# 1-Schematic.net
KiCad netlist of a schematic drawn in EasyEDA
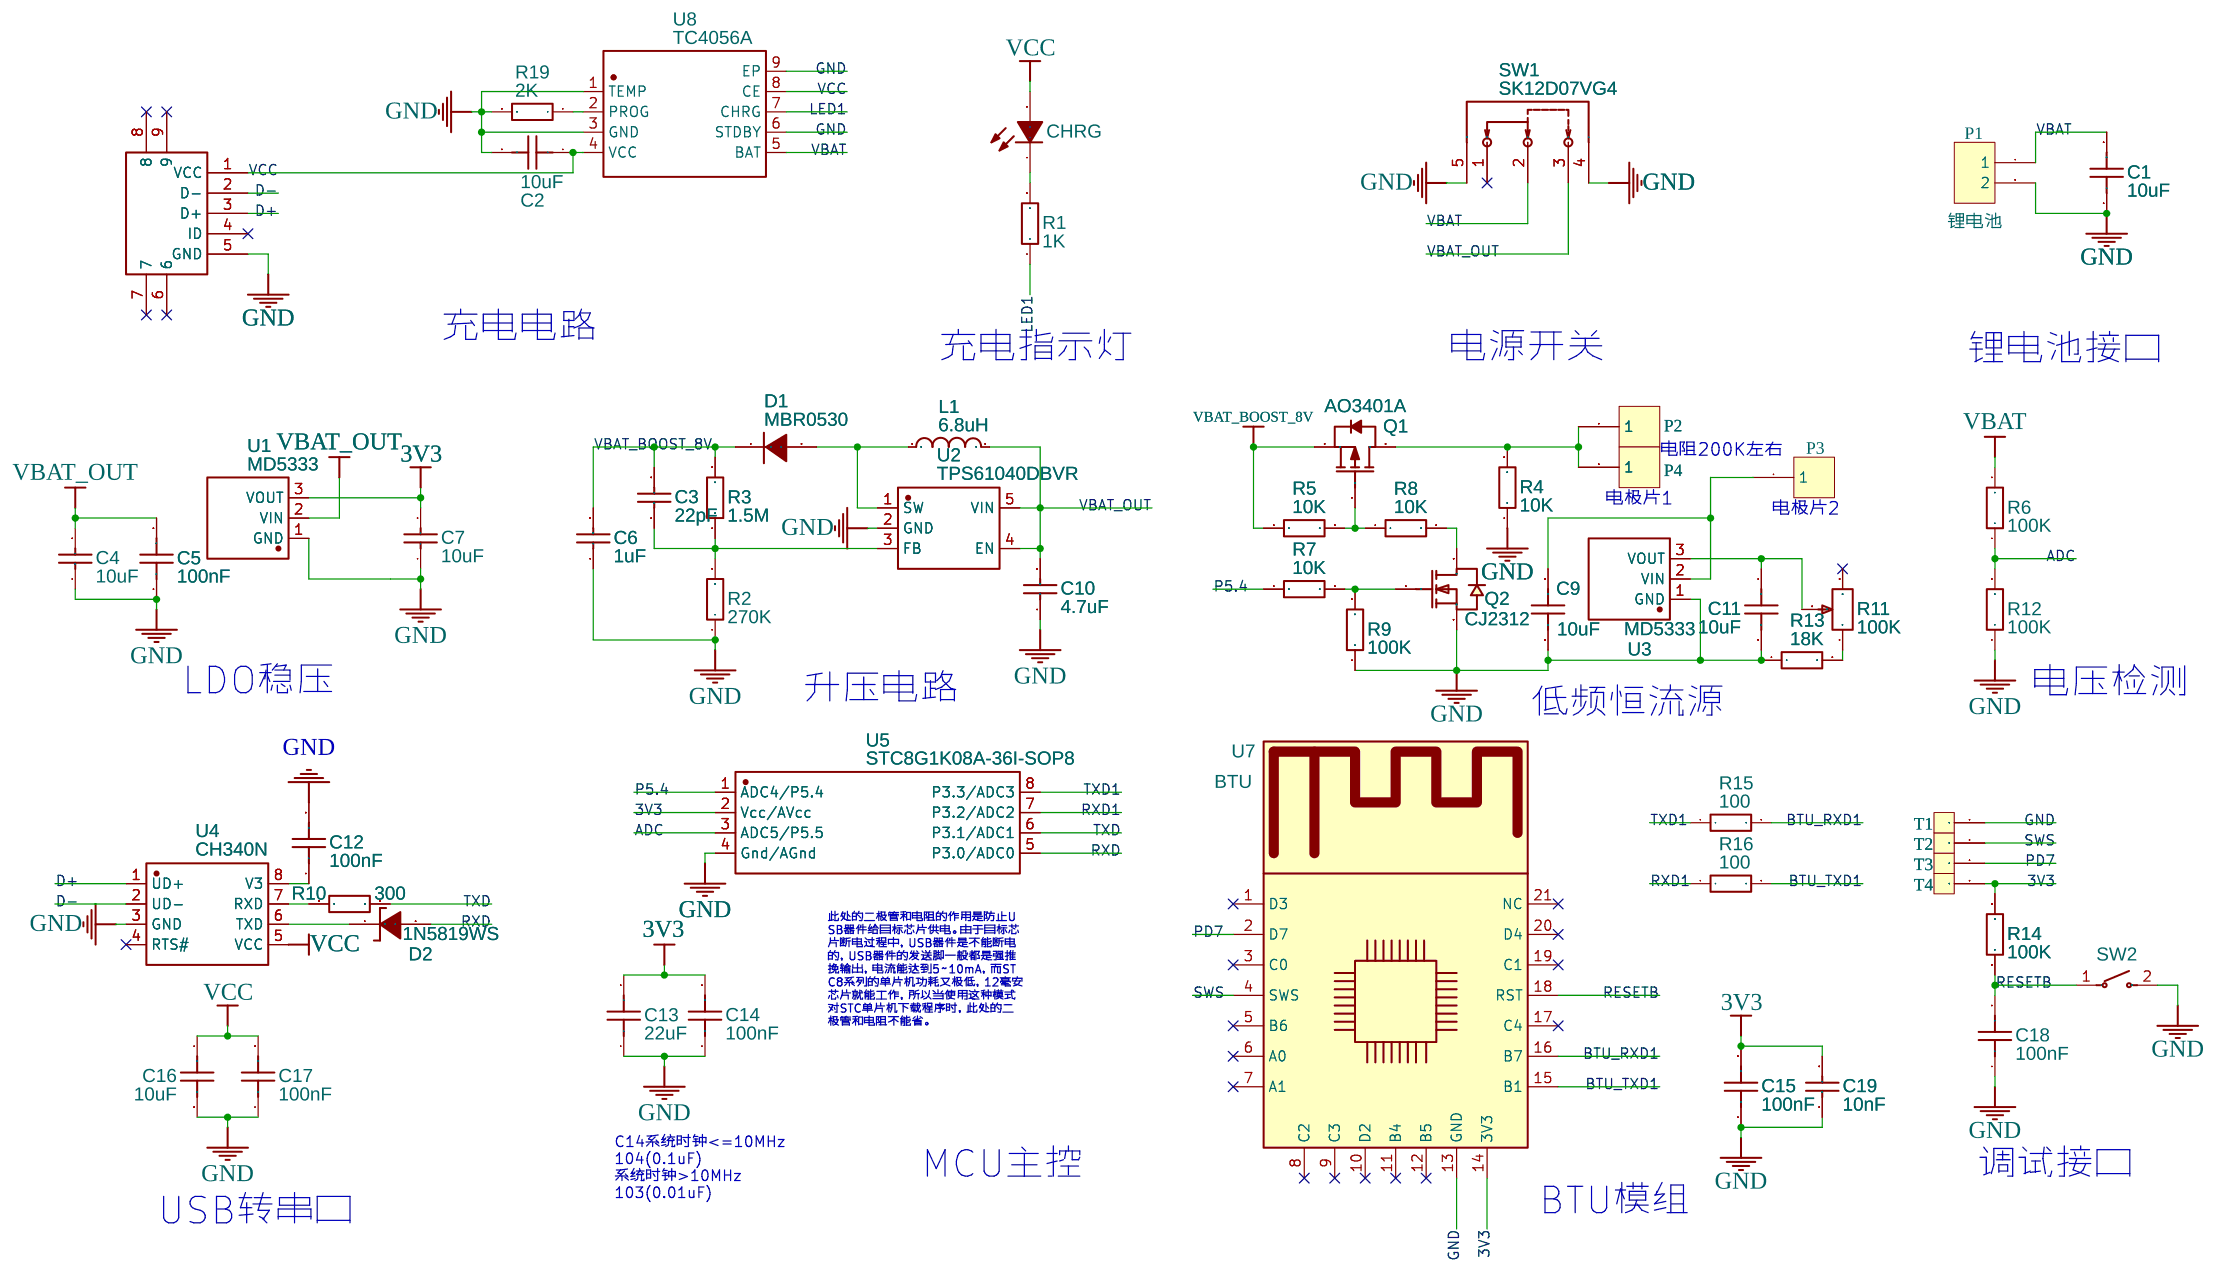
[diagram p0: schematic sheet]

(export (version "E")
  (design (tool "Eeschema 10.0.6"))
  (components
    (comp (ref "C1")
      (value "10uF")
      (fields
        (field (name "BOM_Manufacturer Part") "CL10A106KP8NNNC")
        (field (name "BOM_Supplier Part") "C19702")
      )
      (libsource (lib "") (part "CL10A106KP8NNNC_2"))
    )
    (comp (ref "C2")
      (value "10uF")
      (fields
        (field (name "BOM_Manufacturer Part") "CL10A106KP8NNNC")
        (field (name "BOM_Supplier Part") "C19702")
      )
      (libsource (lib "") (part "CL10A106KP8NNNC"))
    )
    (comp (ref "C3")
      (value "22pF")
      (fields
        (field (name "BOM_Manufacturer Part") "CC0603JRNPO9BN220")
        (field (name "BOM_Supplier Part") "C105620")
      )
      (libsource (lib "") (part "CC0603JRNPO9BN220"))
    )
    (comp (ref "C4")
      (value "10uF")
      (fields
        (field (name "BOM_Manufacturer Part") "CC0603MRX5R6BB106")
        (field (name "BOM_Supplier Part") "C109453")
      )
      (libsource (lib "") (part "CC0603MRX5R6BB106"))
    )
    (comp (ref "C5")
      (value "100nF")
      (fields
        (field (name "BOM_Manufacturer Part") "0603F104Z500")
        (field (name "BOM_Supplier Part") "C83060")
      )
      (libsource (lib "") (part "0603F104Z500"))
    )
    (comp (ref "C6")
      (value "1uF")
      (fields
        (field (name "BOM_Manufacturer Part") "CL10A105KO8NNNC")
        (field (name "BOM_Supplier Part") "C1592")
      )
      (libsource (lib "") (part "CL10A105KO8NNNC"))
    )
    (comp (ref "C7")
      (value "10uF")
      (fields
        (field (name "BOM_Manufacturer Part") "CC0603MRX5R6BB106")
        (field (name "BOM_Supplier Part") "C109453")
      )
      (libsource (lib "") (part "CC0603MRX5R6BB106"))
    )
    (comp (ref "C9")
      (value "10uF")
      (fields
        (field (name "BOM_Manufacturer Part") "CL10A106KP8NNNC")
        (field (name "BOM_Supplier Part") "C19702")
      )
      (libsource (lib "") (part "CL10A106KP8NNNC_1"))
    )
    (comp (ref "C10")
      (value "4.7uF")
      (fields
        (field (name "BOM_Manufacturer Part") "CL10A475KP8NNNC")
        (field (name "BOM_Supplier Part") "C1705")
      )
      (libsource (lib "") (part "CL10A475KP8NNNC"))
    )
    (comp (ref "C11")
      (value "10uF")
      (fields
        (field (name "BOM_Manufacturer Part") "CL10A106KP8NNNC")
        (field (name "BOM_Supplier Part") "C19702")
      )
      (libsource (lib "") (part "CL10A106KP8NNNC_1"))
    )
    (comp (ref "C12")
      (value "100nF")
      (fields
        (field (name "BOM_Manufacturer Part") "CC0603KRX7R9BB104")
        (field (name "BOM_Supplier Part") "C14663")
      )
      (libsource (lib "") (part "CC0603KRX7R9BB104"))
    )
    (comp (ref "C13")
      (value "22uF")
      (fields
        (field (name "BOM_Manufacturer Part") "CL10A226MQ8NRNC")
        (field (name "BOM_Supplier Part") "C59461")
      )
      (libsource (lib "") (part "CL10A226MQ8NRNC"))
    )
    (comp (ref "C14")
      (value "100nF")
      (fields
        (field (name "BOM_Manufacturer Part") "CC0603KRX7R9BB104")
        (field (name "BOM_Supplier Part") "C14663")
      )
      (libsource (lib "") (part "CC0603KRX7R9BB104"))
    )
    (comp (ref "C15")
      (value "100nF")
      (fields
        (field (name "BOM_Manufacturer Part") "CC0603KRX7R9BB104")
        (field (name "BOM_Supplier Part") "C14663")
      )
      (libsource (lib "") (part "CC0603KRX7R9BB104"))
    )
    (comp (ref "C16")
      (value "10uF")
      (fields
        (field (name "BOM_Manufacturer Part") "CL10A106KP8NNNC")
        (field (name "BOM_Supplier Part") "C19702")
      )
      (libsource (lib "") (part "CL10A106KP8NNNC_1"))
    )
    (comp (ref "C17")
      (value "100nF")
      (fields
        (field (name "BOM_Manufacturer Part") "CC0603KRX7R9BB104")
        (field (name "BOM_Supplier Part") "C14663")
      )
      (libsource (lib "") (part "CC0603KRX7R9BB104"))
    )
    (comp (ref "C18")
      (value "100nF")
      (fields
        (field (name "BOM_Manufacturer Part") "CC0603KRX7R9BB104")
        (field (name "BOM_Supplier Part") "C14663")
      )
      (libsource (lib "") (part "CC0603KRX7R9BB104"))
    )
    (comp (ref "C19")
      (value "10nF")
      (fields
        (field (name "BOM_Manufacturer Part") "CC0603KRX7R9BB103")
        (field (name "BOM_Supplier Part") "C100042")
      )
      (libsource (lib "") (part "CC0603KRX7R9BB103"))
    )
    (comp (ref "CHRG")
      (value "19-21SURC/S530-A2/TR8")
      (fields (field (name "BOM_Supplier Part") "C72045"))
      (libsource (lib "") (part "19-21SURC/S530-A2/TR8"))
    )
    (comp (ref "D1")
      (value "MBR0530")
      (fields (field (name "BOM_Supplier Part") "C475718"))
      (libsource (lib "") (part "MBR0530_C475718"))
    )
    (comp (ref "D2")
      (value "1N5819WS")
      (fields (field (name "BOM_Supplier Part") "C191023"))
      (libsource (lib "") (part "1N5819WS"))
    )
    (comp (ref "L1")
      (value "6.8uH")
      (fields
        (field (name "BOM_Manufacturer Part") "CDRH3D23NP-6R8PC")
        (field (name "BOM_Supplier Part") "C323532")
      )
      (libsource (lib "") (part "CDRH3D23NP-6R8PC"))
    )
    (comp (ref "P1") (value "锂电池") (libsource (lib "") (part "Unknown_1010_-650")))
    (comp (ref "P2") (value "CON1") (libsource (lib "") (part "Unknown_825_-520")))
    (comp (ref "P3") (value "CON1") (libsource (lib "") (part "Unknown_911_-495")))
    (comp (ref "P4") (value "CON1") (libsource (lib "") (part "Unknown_825_-500")))
    (comp (ref "Q1")
      (value "AO3401A")
      (fields (field (name "BOM_Supplier Part") "C15127"))
      (libsource (lib "") (part "AO3401A"))
    )
    (comp (ref "Q2")
      (value "CJ2312")
      (fields (field (name "BOM_Supplier Part") "C23521"))
      (libsource (lib "") (part "CJ2312"))
    )
    (comp (ref "R1")
      (value "1K")
      (fields
        (field (name "BOM_Manufacturer Part") "RS-03K1001FT")
        (field (name "BOM_Supplier Part") "C115325")
      )
      (libsource (lib "") (part "RS-03K1001FT"))
    )
    (comp (ref "R2")
      (value "270K")
      (fields
        (field (name "BOM_Manufacturer Part") "0603WAF2703T5E")
        (field (name "BOM_Supplier Part") "C22965")
      )
      (libsource (lib "") (part "0603WAF2703T5E"))
    )
    (comp (ref "R3")
      (value "1.5M")
      (fields
        (field (name "BOM_Manufacturer Part") "0603WAF1504T5E")
        (field (name "BOM_Supplier Part") "C4172")
      )
      (libsource (lib "") (part "0603WAF1504T5E"))
    )
    (comp (ref "R4")
      (value "10K")
      (fields
        (field (name "BOM_Manufacturer Part") "RS-03K103JT")
        (field (name "BOM_Supplier Part") "C73809")
      )
      (libsource (lib "") (part "RS-03K103JT_1"))
    )
    (comp (ref "R5")
      (value "10K")
      (fields
        (field (name "BOM_Manufacturer Part") "RS-03K103JT")
        (field (name "BOM_Supplier Part") "C73809")
      )
      (libsource (lib "") (part "RS-03K103JT"))
    )
    (comp (ref "R6")
      (value "100K")
      (fields
        (field (name "BOM_Manufacturer Part") "RC0603FR-07100KL")
        (field (name "BOM_Supplier Part") "C14675")
      )
      (libsource (lib "") (part "RC0603FR-07100KL"))
    )
    (comp (ref "R7")
      (value "10K")
      (fields
        (field (name "BOM_Manufacturer Part") "RS-03K103JT")
        (field (name "BOM_Supplier Part") "C73809")
      )
      (libsource (lib "") (part "RS-03K103JT"))
    )
    (comp (ref "R8")
      (value "10K")
      (fields
        (field (name "BOM_Manufacturer Part") "RS-03K103JT")
        (field (name "BOM_Supplier Part") "C73809")
      )
      (libsource (lib "") (part "RS-03K103JT"))
    )
    (comp (ref "R9")
      (value "100K")
      (fields
        (field (name "BOM_Manufacturer Part") "RC0603FR-07100KL")
        (field (name "BOM_Supplier Part") "C14675")
      )
      (libsource (lib "") (part "RC0603FR-07100KL"))
    )
    (comp (ref "R10")
      (value "300")
      (fields
        (field (name "BOM_Manufacturer Part") "0603WAF3000T5E")
        (field (name "BOM_Supplier Part") "C23025")
      )
      (libsource (lib "") (part "0603WAF3000T5E"))
    )
    (comp (ref "R11")
      (value "100K")
      (fields
        (field (name "BOM_Manufacturer Part") "VG039NCHXTB104")
        (field (name "BOM_Supplier Part") "C128545")
      )
      (libsource (lib "") (part "VG039NCHXTB104"))
    )
    (comp (ref "R12")
      (value "100K")
      (fields
        (field (name "BOM_Manufacturer Part") "RC0603FR-07100KL")
        (field (name "BOM_Supplier Part") "C14675")
      )
      (libsource (lib "") (part "RC0603FR-07100KL"))
    )
    (comp (ref "R13")
      (value "18K")
      (fields
        (field (name "BOM_Manufacturer Part") "WR06X1502FTL")
        (field (name "BOM_Supplier Part") "C163863")
      )
      (libsource (lib "") (part "WR06X1502FTL"))
    )
    (comp (ref "R14")
      (value "100K")
      (fields
        (field (name "BOM_Manufacturer Part") "RC0603FR-07100KL")
        (field (name "BOM_Supplier Part") "C14675")
      )
      (libsource (lib "") (part "RC0603FR-07100KL"))
    )
    (comp (ref "R15")
      (value "100")
      (fields
        (field (name "BOM_Manufacturer Part") "0603WAJ0101T5E")
        (field (name "BOM_Supplier Part") "C25201")
      )
      (libsource (lib "") (part "0603WAJ0101T5E"))
    )
    (comp (ref "R16")
      (value "100")
      (fields
        (field (name "BOM_Manufacturer Part") "0603WAJ0101T5E")
        (field (name "BOM_Supplier Part") "C25201")
      )
      (libsource (lib "") (part "0603WAJ0101T5E"))
    )
    (comp (ref "R19")
      (value "2K")
      (fields
        (field (name "BOM_Manufacturer Part") "0603WAJ0202T5E")
        (field (name "BOM_Supplier Part") "C25590")
      )
      (libsource (lib "") (part "0603WAJ0202T5E"))
    )
    (comp (ref "SW1")
      (value "SK12D07VG4")
      (fields (field (name "BOM_Supplier Part") "C393937"))
      (libsource (lib "") (part "SK12D07VG4"))
    )
    (comp (ref "SW2")
      (value "TS-1088R-02026")
      (fields (field (name "BOM_Supplier Part") "C455280"))
      (libsource (lib "") (part "TS-1088R-02026"))
    )
    (comp (ref "T1") (value "TP") (libsource (lib "") (part "Unknown_985_-315")))
    (comp (ref "T2") (value "TP") (libsource (lib "") (part "Unknown_985_-305")))
    (comp (ref "T3") (value "TP") (libsource (lib "") (part "Unknown_985_-295")))
    (comp (ref "T4") (value "TP") (libsource (lib "") (part "Unknown_985_-285")))
    (comp (ref "U1")
      (value "MD5333")
      (fields (field (name "BOM_Supplier Part") "C2827936"))
      (libsource (lib "") (part "MD5333"))
    )
    (comp (ref "U2")
      (value "TPS61040DBVR")
      (fields (field (name "BOM_Supplier Part") "C7722"))
      (libsource (lib "") (part "TPS61040DBVR"))
    )
    (comp (ref "U3")
      (value "MD5333")
      (fields (field (name "BOM_Supplier Part") "C2827936"))
      (libsource (lib "") (part "MD5333"))
    )
    (comp (ref "U4")
      (value "CH340N")
      (fields (field (name "BOM_Supplier Part") "C506813"))
      (libsource (lib "") (part "CH340N"))
    )
    (comp (ref "U5")
      (value "STC8G1K08A-36I-SOP8")
      (fields (field (name "BOM_Supplier Part") "C915663"))
      (libsource (lib "") (part "STC8G1K08A-36I-SOP8"))
    )
    (comp (ref "U7") (value "BTU") (libsource (lib "") (part "BTU")))
    (comp (ref "U8")
      (value "TC4056A")
      (fields (field (name "BOM_Supplier Part") "C84051"))
      (libsource (lib "") (part "TC4056A"))
    )
    (comp (ref "USB1")
      (value "U254-051T-4BH23-S2S")
      (fields (field (name "BOM_Supplier Part") "C319163"))
      (libsource (lib "") (part "U254-051T-4BH23-S2S"))
    )
  )
  (nets
    (net (code "1") (name "/ADC") (class "Default")
      (node (ref "R12") (pin "2") (pinfunction "2_2") (pintype "unspecified"))
      (node (ref "R6") (pin "1") (pinfunction "1_1") (pintype "unspecified"))
      (node (ref "U5") (pin "3") (pinfunction "ADC5/P5.5_3") (pintype "unspecified"))
    )
    (net (code "2") (name "/BTU_RXD1") (class "Default")
      (node (ref "R15") (pin "2") (pinfunction "2_2") (pintype "input"))
      (node (ref "U7") (pin "16") (pinfunction "B7_16") (pintype "unspecified"))
    )
    (net (code "3") (name "/BTU_TXD1") (class "Default")
      (node (ref "R16") (pin "2") (pinfunction "2_2") (pintype "input"))
      (node (ref "U7") (pin "15") (pinfunction "B1_15") (pintype "unspecified"))
    )
    (net (code "4") (name "/D+") (class "Default")
      (node (ref "U4") (pin "1") (pinfunction "UD+_1") (pintype "unspecified"))
      (node (ref "USB1") (pin "3") (pinfunction "D+_3") (pintype "unspecified"))
    )
    (net (code "5") (name "/D-") (class "Default")
      (node (ref "U4") (pin "2") (pinfunction "UD-_2") (pintype "unspecified"))
      (node (ref "USB1") (pin "2") (pinfunction "D-_2") (pintype "unspecified"))
    )
    (net (code "6") (name "/LED1") (class "Default")
      (node (ref "R1") (pin "1") (pinfunction "1_1") (pintype "input"))
      (node (ref "U8") (pin "7") (pinfunction "CHRG_7") (pintype "unspecified"))
    )
    (net (code "7") (name "/P5.4") (class "Default")
      (node (ref "R7") (pin "1") (pinfunction "1_1") (pintype "input"))
      (node (ref "U5") (pin "1") (pinfunction "ADC4/P5.4_1") (pintype "unspecified"))
    )
    (net (code "8") (name "/PD7") (class "Default")
      (node (ref "T3") (pin "1") (pinfunction "1_1") (pintype "unspecified"))
      (node (ref "U7") (pin "2") (pinfunction "D7_2") (pintype "unspecified"))
    )
    (net (code "9") (name "/RESETB") (class "Default")
      (node (ref "C18") (pin "2") (pinfunction "2_2") (pintype "unspecified"))
      (node (ref "R14") (pin "1") (pinfunction "1_1") (pintype "unspecified"))
      (node (ref "SW2") (pin "1") (pinfunction "1_1") (pintype "unspecified"))
      (node (ref "U7") (pin "18") (pinfunction "RST_18") (pintype "unspecified"))
    )
    (net (code "10") (name "/RXD") (class "Default")
      (node (ref "D2") (pin "2") (pinfunction "A_2") (pintype "unspecified"))
      (node (ref "U5") (pin "5") (pinfunction "P3.0/ADC0_5") (pintype "unspecified"))
    )
    (net (code "11") (name "/RXD1") (class "Default")
      (node (ref "R16") (pin "1") (pinfunction "1_1") (pintype "input"))
      (node (ref "U5") (pin "7") (pinfunction "P3.2/ADC2_7") (pintype "unspecified"))
    )
    (net (code "12") (name "/SWS") (class "Default")
      (node (ref "T2") (pin "1") (pinfunction "1_1") (pintype "unspecified"))
      (node (ref "U7") (pin "4") (pinfunction "SWS_4") (pintype "unspecified"))
    )
    (net (code "13") (name "/TXD") (class "Default")
      (node (ref "R10") (pin "2") (pinfunction "2_2") (pintype "input"))
      (node (ref "U5") (pin "6") (pinfunction "P3.1/ADC1_6") (pintype "unspecified"))
    )
    (net (code "14") (name "/TXD1") (class "Default")
      (node (ref "R15") (pin "1") (pinfunction "1_1") (pintype "input"))
      (node (ref "U5") (pin "8") (pinfunction "P3.3/ADC3_8") (pintype "unspecified"))
    )
    (net (code "15") (name "3V3") (class "Default")
      (node (ref "C13") (pin "2") (pinfunction "2_2") (pintype "unspecified"))
      (node (ref "C14") (pin "2") (pinfunction "2_2") (pintype "unspecified"))
      (node (ref "C15") (pin "2") (pinfunction "2_2") (pintype "unspecified"))
      (node (ref "C19") (pin "2") (pinfunction "2_2") (pintype "input"))
      (node (ref "C7") (pin "2") (pinfunction "2_2") (pintype "input"))
      (node (ref "R14") (pin "2") (pinfunction "2_2") (pintype "unspecified"))
      (node (ref "T4") (pin "1") (pinfunction "1_1") (pintype "unspecified"))
      (node (ref "U1") (pin "3") (pinfunction "VOUT_3") (pintype "unspecified"))
      (node (ref "U5") (pin "2") (pinfunction "Vcc/AVcc_2") (pintype "unspecified"))
      (node (ref "U7") (pin "14") (pinfunction "3V3_14") (pintype "unspecified"))
    )
    (net (code "16") (name "GND") (class "Default")
      (node (ref "C1") (pin "1") (pinfunction "1_1") (pintype "unspecified"))
      (node (ref "C10") (pin "1") (pinfunction "1_1") (pintype "input"))
      (node (ref "C11") (pin "2") (pinfunction "2_2") (pintype "unspecified"))
      (node (ref "C12") (pin "2") (pinfunction "2_2") (pintype "unspecified"))
      (node (ref "C13") (pin "1") (pinfunction "1_1") (pintype "unspecified"))
      (node (ref "C14") (pin "1") (pinfunction "1_1") (pintype "unspecified"))
      (node (ref "C15") (pin "1") (pinfunction "1_1") (pintype "unspecified"))
      (node (ref "C16") (pin "2") (pinfunction "2_2") (pintype "unspecified"))
      (node (ref "C17") (pin "1") (pinfunction "1_1") (pintype "unspecified"))
      (node (ref "C18") (pin "1") (pinfunction "1_1") (pintype "unspecified"))
      (node (ref "C19") (pin "1") (pinfunction "1_1") (pintype "input"))
      (node (ref "C2") (pin "2") (pinfunction "2_2") (pintype "unspecified"))
      (node (ref "C4") (pin "1") (pinfunction "1_1") (pintype "input"))
      (node (ref "C5") (pin "1") (pinfunction "1_1") (pintype "unspecified"))
      (node (ref "C6") (pin "1") (pinfunction "1_1") (pintype "input"))
      (node (ref "C7") (pin "1") (pinfunction "1_1") (pintype "input"))
      (node (ref "C9") (pin "2") (pinfunction "2_2") (pintype "unspecified"))
      (node (ref "P1") (pin "2") (pinfunction "2_2") (pintype "unspecified"))
      (node (ref "Q2") (pin "2") (pinfunction "S_2") (pintype "unspecified"))
      (node (ref "R12") (pin "1") (pinfunction "1_1") (pintype "unspecified"))
      (node (ref "R13") (pin "1") (pinfunction "1_1") (pintype "unspecified"))
      (node (ref "R19") (pin "2") (pinfunction "2_2") (pintype "input"))
      (node (ref "R2") (pin "1") (pinfunction "1_1") (pintype "input"))
      (node (ref "R4") (pin "1") (pinfunction "1_1") (pintype "input"))
      (node (ref "R9") (pin "1") (pinfunction "1_1") (pintype "unspecified"))
      (node (ref "SW1") (pin "4") (pinfunction "4_4") (pintype "unspecified"))
      (node (ref "SW1") (pin "5") (pinfunction "5_5") (pintype "unspecified"))
      (node (ref "SW2") (pin "2") (pinfunction "2_2") (pintype "unspecified"))
      (node (ref "T1") (pin "1") (pinfunction "1_1") (pintype "unspecified"))
      (node (ref "U1") (pin "1") (pinfunction "GND_1") (pintype "unspecified"))
      (node (ref "U2") (pin "2") (pinfunction "GND_2") (pintype "unspecified"))
      (node (ref "U3") (pin "1") (pinfunction "GND_1") (pintype "unspecified"))
      (node (ref "U4") (pin "3") (pinfunction "GND_3") (pintype "unspecified"))
      (node (ref "U5") (pin "4") (pinfunction "Gnd/AGnd_4") (pintype "unspecified"))
      (node (ref "U7") (pin "13") (pinfunction "GND_13") (pintype "unspecified"))
      (node (ref "U8") (pin "1") (pinfunction "TEMP_1") (pintype "unspecified"))
      (node (ref "U8") (pin "3") (pinfunction "GND_3") (pintype "unspecified"))
      (node (ref "U8") (pin "6") (pinfunction "STDBY_6") (pintype "unspecified"))
      (node (ref "U8") (pin "9") (pinfunction "EP_9") (pintype "unspecified"))
      (node (ref "USB1") (pin "5") (pinfunction "GND_5") (pintype "unspecified"))
    )
    (net (code "17") (name "Net-(CHRG--)") (class "Default")
      (node (ref "CHRG") (pin "1") (pinfunction "-_1") (pintype "input"))
      (node (ref "R1") (pin "2") (pinfunction "2_2") (pintype "input"))
    )
    (net (code "18") (name "Net-(D1-A)") (class "Default")
      (node (ref "D1") (pin "2") (pinfunction "A_2") (pintype "unspecified"))
      (node (ref "L1") (pin "1") (pinfunction "1_1") (pintype "unspecified"))
      (node (ref "U2") (pin "1") (pinfunction "SW_1") (pintype "unspecified"))
    )
    (net (code "19") (name "Net-(D2-C)") (class "Default")
      (node (ref "D2") (pin "1") (pinfunction "C_1") (pintype "unspecified"))
      (node (ref "U4") (pin "6") (pinfunction "TXD_6") (pintype "unspecified"))
    )
    (net (code "20") (name "Net-(Q1-D)") (class "Default")
      (node (ref "P2") (pin "1") (pinfunction "1_1") (pintype "unspecified"))
      (node (ref "P4") (pin "1") (pinfunction "1_1") (pintype "unspecified"))
      (node (ref "Q1") (pin "3") (pinfunction "D_3") (pintype "unspecified"))
      (node (ref "R4") (pin "2") (pinfunction "2_2") (pintype "input"))
    )
    (net (code "21") (name "Net-(Q1-G)") (class "Default")
      (node (ref "Q1") (pin "1") (pinfunction "G_1") (pintype "unspecified"))
      (node (ref "R5") (pin "2") (pinfunction "2_2") (pintype "input"))
      (node (ref "R8") (pin "1") (pinfunction "1_1") (pintype "input"))
    )
    (net (code "22") (name "Net-(Q2-D)") (class "Default")
      (node (ref "Q2") (pin "3") (pinfunction "D_3") (pintype "unspecified"))
      (node (ref "R8") (pin "2") (pinfunction "2_2") (pintype "input"))
    )
    (net (code "23") (name "Net-(Q2-G)") (class "Default")
      (node (ref "Q2") (pin "1") (pinfunction "G_1") (pintype "unspecified"))
      (node (ref "R7") (pin "2") (pinfunction "2_2") (pintype "input"))
      (node (ref "R9") (pin "2") (pinfunction "2_2") (pintype "unspecified"))
    )
    (net (code "24") (name "Net-(R11-Pad1)") (class "Default")
      (node (ref "R11") (pin "1") (pinfunction "1_1") (pintype "input"))
      (node (ref "R13") (pin "2") (pinfunction "2_2") (pintype "unspecified"))
    )
    (net (code "25") (name "Net-(U2-FB)") (class "Default")
      (node (ref "C3") (pin "1") (pinfunction "1_1") (pintype "input"))
      (node (ref "R2") (pin "2") (pinfunction "2_2") (pintype "input"))
      (node (ref "R3") (pin "1") (pinfunction "1_1") (pintype "input"))
      (node (ref "U2") (pin "3") (pinfunction "FB_3") (pintype "unspecified"))
    )
    (net (code "26") (name "Net-(U3-VIN)") (class "Default")
      (node (ref "C9") (pin "1") (pinfunction "1_1") (pintype "unspecified"))
      (node (ref "P3") (pin "1") (pinfunction "1_1") (pintype "unspecified"))
      (node (ref "U3") (pin "2") (pinfunction "VIN_2") (pintype "unspecified"))
    )
    (net (code "27") (name "Net-(U3-VOUT)") (class "Default")
      (node (ref "C11") (pin "1") (pinfunction "1_1") (pintype "unspecified"))
      (node (ref "R11") (pin "2") (pinfunction "2_2") (pintype "input"))
      (node (ref "U3") (pin "3") (pinfunction "VOUT_3") (pintype "unspecified"))
    )
    (net (code "28") (name "Net-(U4-RXD)") (class "Default")
      (node (ref "R10") (pin "1") (pinfunction "1_1") (pintype "input"))
      (node (ref "U4") (pin "7") (pinfunction "RXD_7") (pintype "unspecified"))
    )
    (net (code "29") (name "Net-(U4-V3)") (class "Default")
      (node (ref "C12") (pin "1") (pinfunction "1_1") (pintype "unspecified"))
      (node (ref "U4") (pin "8") (pinfunction "V3_8") (pintype "unspecified"))
    )
    (net (code "30") (name "Net-(U8-PROG)") (class "Default")
      (node (ref "R19") (pin "1") (pinfunction "1_1") (pintype "input"))
      (node (ref "U8") (pin "2") (pinfunction "PROG_2") (pintype "unspecified"))
    )
    (net (code "31") (name "VBAT") (class "Default")
      (node (ref "C1") (pin "2") (pinfunction "2_2") (pintype "unspecified"))
      (node (ref "P1") (pin "1") (pinfunction "1_1") (pintype "unspecified"))
      (node (ref "R6") (pin "2") (pinfunction "2_2") (pintype "unspecified"))
      (node (ref "SW1") (pin "2") (pinfunction "2_2") (pintype "unspecified"))
      (node (ref "U8") (pin "5") (pinfunction "BAT_5") (pintype "unspecified"))
    )
    (net (code "32") (name "VBAT_BOOST_8V") (class "Default")
      (node (ref "C3") (pin "2") (pinfunction "2_2") (pintype "input"))
      (node (ref "C6") (pin "2") (pinfunction "2_2") (pintype "input"))
      (node (ref "D1") (pin "1") (pinfunction "K_1") (pintype "unspecified"))
      (node (ref "Q1") (pin "2") (pinfunction "S_2") (pintype "unspecified"))
      (node (ref "R3") (pin "2") (pinfunction "2_2") (pintype "input"))
      (node (ref "R5") (pin "1") (pinfunction "1_1") (pintype "input"))
    )
    (net (code "33") (name "VBAT_OUT") (class "Default")
      (node (ref "C10") (pin "2") (pinfunction "2_2") (pintype "input"))
      (node (ref "C4") (pin "2") (pinfunction "2_2") (pintype "input"))
      (node (ref "C5") (pin "2") (pinfunction "2_2") (pintype "unspecified"))
      (node (ref "L1") (pin "2") (pinfunction "2_2") (pintype "unspecified"))
      (node (ref "SW1") (pin "3") (pinfunction "3_3") (pintype "unspecified"))
      (node (ref "U1") (pin "2") (pinfunction "VIN_2") (pintype "unspecified"))
      (node (ref "U2") (pin "4") (pinfunction "EN_4") (pintype "unspecified"))
      (node (ref "U2") (pin "5") (pinfunction "VIN_5") (pintype "unspecified"))
    )
    (net (code "34") (name "VCC") (class "Default")
      (node (ref "C16") (pin "1") (pinfunction "1_1") (pintype "unspecified"))
      (node (ref "C17") (pin "2") (pinfunction "2_2") (pintype "unspecified"))
      (node (ref "C2") (pin "1") (pinfunction "1_1") (pintype "unspecified"))
      (node (ref "CHRG") (pin "2") (pinfunction "+_2") (pintype "input"))
      (node (ref "U4") (pin "5") (pinfunction "VCC_5") (pintype "unspecified"))
      (node (ref "U8") (pin "4") (pinfunction "VCC_4") (pintype "unspecified"))
      (node (ref "U8") (pin "8") (pinfunction "CE_8") (pintype "unspecified"))
      (node (ref "USB1") (pin "1") (pinfunction "VCC_1") (pintype "unspecified"))
    )
    (net (code "35") (name "unconnected-(R11-Pad3)") (class "Default")
      (node (ref "R11") (pin "3") (pinfunction "3_3") (pintype "input+no_connect"))
    )
    (net (code "36") (name "unconnected-(SW1-Pad1)") (class "Default")
      (node (ref "SW1") (pin "1") (pinfunction "1_1") (pintype "unspecified+no_connect"))
    )
    (net (code "37") (name "unconnected-(U4-RTS#-Pad4)") (class "Default")
      (node (ref "U4") (pin "4") (pinfunction "RTS#_4") (pintype "unspecified+no_connect"))
    )
    (net (code "38") (name "unconnected-(U7-A0-Pad6)") (class "Default")
      (node (ref "U7") (pin "6") (pinfunction "A0_6") (pintype "unspecified+no_connect"))
    )
    (net (code "39") (name "unconnected-(U7-A1-Pad7)") (class "Default")
      (node (ref "U7") (pin "7") (pinfunction "A1_7") (pintype "unspecified+no_connect"))
    )
    (net (code "40") (name "unconnected-(U7-B4-Pad11)") (class "Default")
      (node (ref "U7") (pin "11") (pinfunction "B4_11") (pintype "unspecified+no_connect"))
    )
    (net (code "41") (name "unconnected-(U7-B5-Pad12)") (class "Default")
      (node (ref "U7") (pin "12") (pinfunction "B5_12") (pintype "unspecified+no_connect"))
    )
    (net (code "42") (name "unconnected-(U7-B6-Pad5)") (class "Default")
      (node (ref "U7") (pin "5") (pinfunction "B6_5") (pintype "unspecified+no_connect"))
    )
    (net (code "43") (name "unconnected-(U7-C0-Pad3)") (class "Default")
      (node (ref "U7") (pin "3") (pinfunction "C0_3") (pintype "unspecified+no_connect"))
    )
    (net (code "44") (name "unconnected-(U7-C1-Pad19)") (class "Default")
      (node (ref "U7") (pin "19") (pinfunction "C1_19") (pintype "unspecified+no_connect"))
    )
    (net (code "45") (name "unconnected-(U7-C2-Pad8)") (class "Default")
      (node (ref "U7") (pin "8") (pinfunction "C2_8") (pintype "unspecified+no_connect"))
    )
    (net (code "46") (name "unconnected-(U7-C3-Pad9)") (class "Default")
      (node (ref "U7") (pin "9") (pinfunction "C3_9") (pintype "unspecified+no_connect"))
    )
    (net (code "47") (name "unconnected-(U7-C4-Pad17)") (class "Default")
      (node (ref "U7") (pin "17") (pinfunction "C4_17") (pintype "unspecified+no_connect"))
    )
    (net (code "48") (name "unconnected-(U7-D2-Pad10)") (class "Default")
      (node (ref "U7") (pin "10") (pinfunction "D2_10") (pintype "unspecified+no_connect"))
    )
    (net (code "49") (name "unconnected-(U7-D3-Pad1)") (class "Default")
      (node (ref "U7") (pin "1") (pinfunction "D3_1") (pintype "unspecified+no_connect"))
    )
    (net (code "50") (name "unconnected-(U7-D4-Pad20)") (class "Default")
      (node (ref "U7") (pin "20") (pinfunction "D4_20") (pintype "unspecified+no_connect"))
    )
    (net (code "51") (name "unconnected-(U7-NC-Pad21)") (class "Default")
      (node (ref "U7") (pin "21") (pinfunction "NC_21") (pintype "unspecified+no_connect"))
    )
    (net (code "52") (name "unconnected-(USB1-ID-Pad4)") (class "Default")
      (node (ref "USB1") (pin "4") (pinfunction "ID_4") (pintype "unspecified+no_connect"))
    )
    (net (code "53") (name "unconnected-(USB1-Pad6)") (class "Default")
      (node (ref "USB1") (pin "6") (pinfunction "6_6") (pintype "unspecified+no_connect"))
    )
    (net (code "54") (name "unconnected-(USB1-Pad7)") (class "Default")
      (node (ref "USB1") (pin "7") (pinfunction "7_7") (pintype "unspecified+no_connect"))
    )
    (net (code "55") (name "unconnected-(USB1-Pad8)") (class "Default")
      (node (ref "USB1") (pin "8") (pinfunction "8_8") (pintype "unspecified+no_connect"))
    )
    (net (code "56") (name "unconnected-(USB1-Pad9)") (class "Default")
      (node (ref "USB1") (pin "9") (pinfunction "9_9") (pintype "unspecified+no_connect"))
    )
  )
)
